# PCAL9539A_16-bit_Port_Expander.net
KiCad netlist of a schematic drawn in Altium Designer
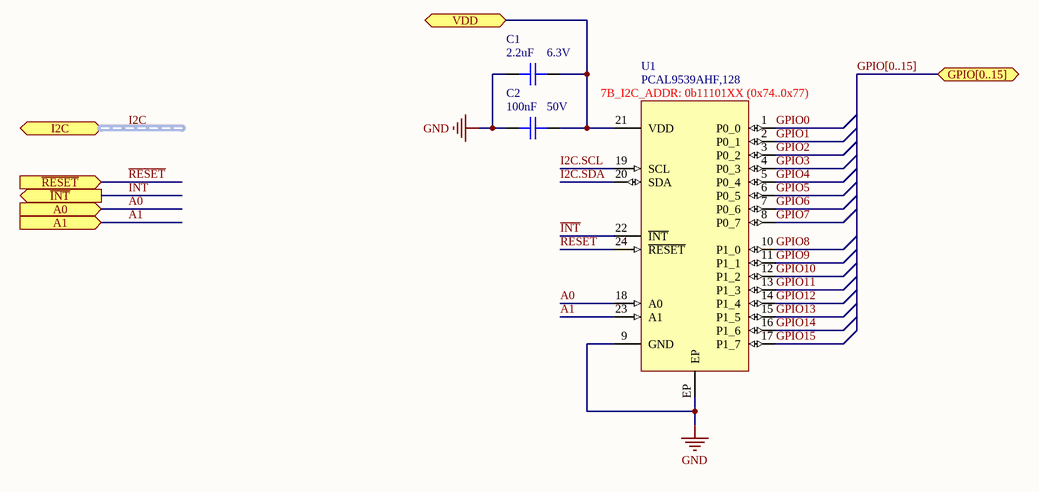
[diagram p0: PCAL9539A_16-bit_Port_Expander.SchDoc]

(export (version "E")
  (design (tool "Eeschema 10.0.6"))
  (components
    (comp (ref "C1")
      (value "CAP CER 2.2UF 6.3V X5R 0402")
      (footprint "C0402")
      (description "2.2µF ±20% 6.3V Ceramic Capacitor X5R 0402 (1005 Metric)")
      (fields
        (field (name "MANUFACTURER") "Murata")
        (field (name "MANUFACTURER PART NUMBER") "GRM155R60J225ME15D")
        (field (name "CAPACITANCE") "2.2uF")
        (field (name "VOLTAGE") "6.3V")
      )
      (libsource (lib "capacitors_smd") (part "CAP CER 2.2UF 6.3V X5R 0402"))
    )
    (comp (ref "C2")
      (value "CAP CER 0.1UF 50V X7R 0402")
      (footprint "C0402")
      (description "0.1µF ±10% 50V Ceramic Capacitor X7R 0402 (1005 Metric)")
      (fields
        (field (name "MANUFACTURER") "TDK")
        (field (name "MANUFACTURER PART NUMBER") "CGA2B3X7R1H104K050BB")
        (field (name "CAPACITANCE") "100nF")
        (field (name "VOLTAGE") "50V")
      )
      (libsource (lib "capacitors_smd") (part "CAP CER 0.1UF 50V X7R 0402"))
    )
    (comp (ref "U1")
      (value "PCAL9539AHF,128")
      (footprint "QFN-EP 24")
      (description "I/O Expander with interrupt and reset 16 I²C 400kHz 24-HWQFN (4x4)")
      (fields
        (field (name "MANUFACTURER") "NXP Semiconductors")
        (field (name "7B_I2C_ADDR") "0b11101XX (0x74..0x77)")
      )
      (libsource (lib "ic_i2c_interface") (part "IC PCAL9539AHF,128 I/O EXPANDER 16BIT 24HWQFN"))
    )
  )
  (nets
    (net (code "2") (name "/A0") (class "Default")
      (node (ref "U1") (pin "18") (pinfunction "A0_18") (pintype "input"))
    )
    (net (code "3") (name "/A1") (class "Default")
      (node (ref "U1") (pin "23") (pinfunction "A1_23") (pintype "input"))
    )
    (net (code "4") (name "/GPIO0") (class "Default")
      (node (ref "U1") (pin "1") (pinfunction "P0_0_1") (pintype "bidirectional"))
    )
    (net (code "5") (name "/GPIO1") (class "Default")
      (node (ref "U1") (pin "2") (pinfunction "P0_1_2") (pintype "bidirectional"))
    )
    (net (code "6") (name "/GPIO2") (class "Default")
      (node (ref "U1") (pin "3") (pinfunction "P0_2_3") (pintype "bidirectional"))
    )
    (net (code "7") (name "/GPIO3") (class "Default")
      (node (ref "U1") (pin "4") (pinfunction "P0_3_4") (pintype "bidirectional"))
    )
    (net (code "8") (name "/GPIO4") (class "Default")
      (node (ref "U1") (pin "5") (pinfunction "P0_4_5") (pintype "bidirectional"))
    )
    (net (code "9") (name "/GPIO5") (class "Default")
      (node (ref "U1") (pin "6") (pinfunction "P0_5_6") (pintype "bidirectional"))
    )
    (net (code "10") (name "/GPIO6") (class "Default")
      (node (ref "U1") (pin "7") (pinfunction "P0_6_7") (pintype "bidirectional"))
    )
    (net (code "11") (name "/GPIO7") (class "Default")
      (node (ref "U1") (pin "8") (pinfunction "P0_7_8") (pintype "bidirectional"))
    )
    (net (code "12") (name "/GPIO8") (class "Default")
      (node (ref "U1") (pin "10") (pinfunction "P1_0_10") (pintype "bidirectional"))
    )
    (net (code "13") (name "/GPIO9") (class "Default")
      (node (ref "U1") (pin "11") (pinfunction "P1_1_11") (pintype "bidirectional"))
    )
    (net (code "14") (name "/GPIO10") (class "Default")
      (node (ref "U1") (pin "12") (pinfunction "P1_2_12") (pintype "bidirectional"))
    )
    (net (code "15") (name "/GPIO11") (class "Default")
      (node (ref "U1") (pin "13") (pinfunction "P1_3_13") (pintype "bidirectional"))
    )
    (net (code "16") (name "/GPIO12") (class "Default")
      (node (ref "U1") (pin "14") (pinfunction "P1_4_14") (pintype "bidirectional"))
    )
    (net (code "17") (name "/GPIO13") (class "Default")
      (node (ref "U1") (pin "15") (pinfunction "P1_5_15") (pintype "bidirectional"))
    )
    (net (code "18") (name "/GPIO14") (class "Default")
      (node (ref "U1") (pin "16") (pinfunction "P1_6_16") (pintype "bidirectional"))
    )
    (net (code "19") (name "/GPIO15") (class "Default")
      (node (ref "U1") (pin "17") (pinfunction "P1_7_17") (pintype "bidirectional"))
    )
    (net (code "21") (name "/I2C.SCL") (class "Default")
      (node (ref "U1") (pin "19") (pinfunction "SCL_19") (pintype "input"))
    )
    (net (code "22") (name "/I2C.SDA") (class "Default")
      (node (ref "U1") (pin "20") (pinfunction "SDA_20") (pintype "bidirectional"))
    )
    (net (code "23") (name "/INT") (class "Default")
      (node (ref "U1") (pin "22") (pinfunction "~{INT}_22") (pintype "open_collector"))
    )
    (net (code "24") (name "/RESET") (class "Default")
      (node (ref "U1") (pin "24") (pinfunction "~{RESET}_24") (pintype "input"))
    )
    (net (code "25") (name "/VDD") (class "Default")
      (node (ref "C1") (pin "1") (pinfunction "1_1") (pintype "passive"))
      (node (ref "C2") (pin "1") (pinfunction "1_1") (pintype "passive"))
      (node (ref "U1") (pin "21") (pinfunction "VDD_21") (pintype "power_in"))
    )
    (net (code "27") (name "GND") (class "Default")
      (node (ref "C1") (pin "2") (pinfunction "2_2") (pintype "passive"))
      (node (ref "C2") (pin "2") (pinfunction "2_2") (pintype "passive"))
      (node (ref "U1") (pin "9") (pinfunction "GND_9") (pintype "power_in"))
      (node (ref "U1") (pin "EP") (pinfunction "EP_EP") (pintype "power_in"))
    )
  )
)
